# qbI0000115v1_1_1.net
KiCad netlist of a schematic drawn in Altium Designer
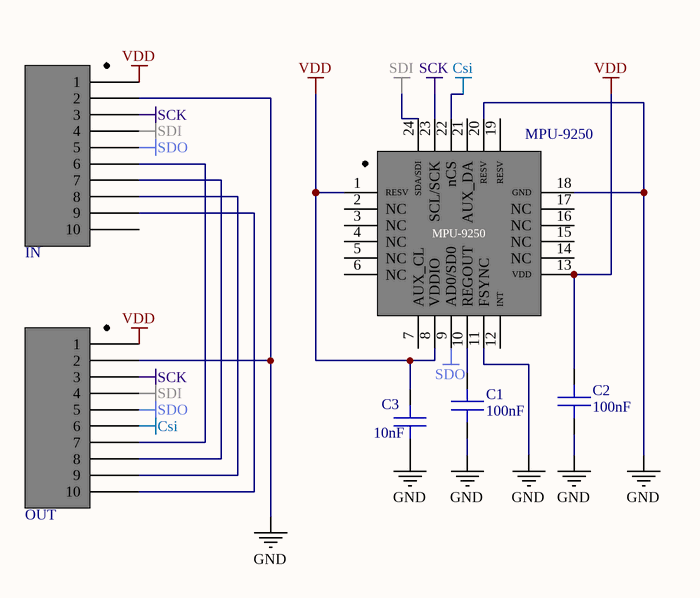
[diagram p0: qbI0000115v1.1.1.SchDoc]

(export (version "E")
  (design (tool "Eeschema 10.0.6"))
  (components
    (comp (ref "C1")
      (value "100nF")
      (footprint "C0603C104K5RACAUTO")
      (description "KEMET 100nF 0603 Cer 50VDC 10% X7R MLCC")
      (libsource (lib "Additional custom library") (part "C0603C104K5RACAUTO"))
    )
    (comp (ref "C2")
      (value "100nF")
      (footprint "C0603C104K5RACAUTO")
      (description "KEMET 100nF 0603 Cer 50VDC 10% X7R MLCC")
      (libsource (lib "Additional custom library") (part "C0603C104K5RACAUTO"))
    )
    (comp (ref "C3")
      (value "10nF")
      (footprint "C0603C103J8RACTU")
      (description "Kemet C 10nF 0603 Cer 10VDC 5% X7R MLCC")
      (fields
        (field (name "MANUFACTURER") "Kemet")
        (field (name "MANUFACTURER PART NUMBER") "C0603C103J8RACTU")
      )
      (libsource (lib "qbCapacitor0603") (part "C0603C103J8RACTU"))
    )
    (comp (ref "IN")
      (value "JST SM10B-XSRS-ETB")
      (footprint "SM10B-XSRS-ETB")
      (description "JST 10WAY angle XSR, SMT, 0.6mm, SM10B-XSRS-ETB")
      (fields (field (name "MANUFACTURER") "JST") (field (name "MANUFACTURER PART NUMBER") "SM10B-XSRS-ETB"))
      (libsource (lib "QB Conn Lib") (part "SM10B-XSRS-ETB"))
    )
    (comp (ref "MPU-9250")
      (value "MPU-9250")
      (footprint "MPU-2950")
      (description "MPU-9250 3X3X1 24QFN")
      (fields (field (name "MANUFACTURER") "InvenSense"))
      (libsource (lib "qbChipset") (part "MPU-9250"))
    )
    (comp (ref "OUT")
      (value "JST SM10B-XSRS-ETB")
      (footprint "SM10B-XSRS-ETB")
      (description "JST 10WAY angle XSR, SMT, 0.6mm, SM10B-XSRS-ETB")
      (fields (field (name "MANUFACTURER") "JST") (field (name "MANUFACTURER PART NUMBER") "SM10B-XSRS-ETB"))
      (libsource (lib "QB Conn Lib") (part "SM10B-XSRS-ETB"))
    )
  )
  (nets
    (net (code "1") (name "Csi") (class "Default")
      (node (ref "MPU-9250") (pin "22") (pinfunction "nCS_22") (pintype "passive"))
      (node (ref "OUT") (pin "6") (pinfunction "6_6") (pintype "passive"))
    )
    (net (code "2") (name "GND") (class "Default")
      (node (ref "C1") (pin "1") (pinfunction "1_1") (pintype "passive"))
      (node (ref "C2") (pin "1") (pinfunction "1_1") (pintype "passive"))
      (node (ref "C3") (pin "1") (pinfunction "1_1") (pintype "passive"))
      (node (ref "IN") (pin "2") (pinfunction "2_2") (pintype "passive"))
      (node (ref "MPU-9250") (pin "11") (pinfunction "FSYNC_11") (pintype "passive"))
      (node (ref "MPU-9250") (pin "18") (pinfunction "GND_18") (pintype "passive"))
      (node (ref "MPU-9250") (pin "20") (pinfunction "RESV_20") (pintype "passive"))
      (node (ref "OUT") (pin "2") (pinfunction "2_2") (pintype "passive"))
    )
    (net (code "3") (name "Net-(IN-Pad6)") (class "Default")
      (node (ref "IN") (pin "6") (pinfunction "6_6") (pintype "passive"))
      (node (ref "OUT") (pin "7") (pinfunction "7_7") (pintype "passive"))
    )
    (net (code "4") (name "Net-(IN-Pad7)") (class "Default")
      (node (ref "IN") (pin "7") (pinfunction "7_7") (pintype "passive"))
      (node (ref "OUT") (pin "8") (pinfunction "8_8") (pintype "passive"))
    )
    (net (code "5") (name "Net-(IN-Pad8)") (class "Default")
      (node (ref "IN") (pin "8") (pinfunction "8_8") (pintype "passive"))
      (node (ref "OUT") (pin "9") (pinfunction "9_9") (pintype "passive"))
    )
    (net (code "6") (name "Net-(IN-Pad9)") (class "Default")
      (node (ref "IN") (pin "9") (pinfunction "9_9") (pintype "passive"))
      (node (ref "OUT") (pin "10") (pinfunction "10_10") (pintype "passive"))
    )
    (net (code "7") (name "Net-(MPU-9250-REGOUT)") (class "Default")
      (node (ref "C1") (pin "2") (pinfunction "2_2") (pintype "passive"))
      (node (ref "MPU-9250") (pin "10") (pinfunction "REGOUT_10") (pintype "passive"))
    )
    (net (code "8") (name "SCK") (class "Default")
      (node (ref "IN") (pin "3") (pinfunction "3_3") (pintype "passive"))
      (node (ref "MPU-9250") (pin "23") (pinfunction "SCL/SCK_23") (pintype "passive"))
      (node (ref "OUT") (pin "3") (pinfunction "3_3") (pintype "passive"))
    )
    (net (code "9") (name "SDI") (class "Default")
      (node (ref "IN") (pin "4") (pinfunction "4_4") (pintype "passive"))
      (node (ref "MPU-9250") (pin "24") (pinfunction "SDA/SDI_24") (pintype "passive"))
      (node (ref "OUT") (pin "4") (pinfunction "4_4") (pintype "passive"))
    )
    (net (code "10") (name "SDO") (class "Default")
      (node (ref "IN") (pin "5") (pinfunction "5_5") (pintype "passive"))
      (node (ref "MPU-9250") (pin "9") (pinfunction "AD0/SD0_9") (pintype "passive"))
      (node (ref "OUT") (pin "5") (pinfunction "5_5") (pintype "passive"))
    )
    (net (code "11") (name "VDD") (class "Default")
      (node (ref "C2") (pin "2") (pinfunction "2_2") (pintype "passive"))
      (node (ref "C3") (pin "2") (pinfunction "2_2") (pintype "passive"))
      (node (ref "IN") (pin "1") (pinfunction "1_1") (pintype "passive"))
      (node (ref "MPU-9250") (pin "1") (pinfunction "RESV_1") (pintype "passive"))
      (node (ref "MPU-9250") (pin "13") (pinfunction "VDD_13") (pintype "passive"))
      (node (ref "MPU-9250") (pin "8") (pinfunction "VDDIO_8") (pintype "passive"))
      (node (ref "OUT") (pin "1") (pinfunction "1_1") (pintype "passive"))
    )
    (net (code "12") (name "unconnected-(IN-Pad10)") (class "Default")
      (node (ref "IN") (pin "10") (pinfunction "10_10") (pintype "passive"))
    )
    (net (code "13") (name "unconnected-(MPU-9250-AUX_CL-Pad7)") (class "Default")
      (node (ref "MPU-9250") (pin "7") (pinfunction "AUX_CL_7") (pintype "passive"))
    )
    (net (code "14") (name "unconnected-(MPU-9250-AUX_DA-Pad21)") (class "Default")
      (node (ref "MPU-9250") (pin "21") (pinfunction "AUX_DA_21") (pintype "passive"))
    )
    (net (code "15") (name "unconnected-(MPU-9250-INT-Pad12)") (class "Default")
      (node (ref "MPU-9250") (pin "12") (pinfunction "INT_12") (pintype "passive"))
    )
    (net (code "16") (name "unconnected-(MPU-9250-NC-Pad2)") (class "Default")
      (node (ref "MPU-9250") (pin "2") (pinfunction "NC_2") (pintype "passive"))
    )
    (net (code "17") (name "unconnected-(MPU-9250-NC-Pad3)") (class "Default")
      (node (ref "MPU-9250") (pin "3") (pinfunction "NC_3") (pintype "passive"))
    )
    (net (code "18") (name "unconnected-(MPU-9250-NC-Pad4)") (class "Default")
      (node (ref "MPU-9250") (pin "4") (pinfunction "NC_4") (pintype "passive"))
    )
    (net (code "19") (name "unconnected-(MPU-9250-NC-Pad5)") (class "Default")
      (node (ref "MPU-9250") (pin "5") (pinfunction "NC_5") (pintype "passive"))
    )
    (net (code "20") (name "unconnected-(MPU-9250-NC-Pad6)") (class "Default")
      (node (ref "MPU-9250") (pin "6") (pinfunction "NC_6") (pintype "passive"))
    )
    (net (code "21") (name "unconnected-(MPU-9250-NC-Pad14)") (class "Default")
      (node (ref "MPU-9250") (pin "14") (pinfunction "NC_14") (pintype "passive"))
    )
    (net (code "22") (name "unconnected-(MPU-9250-NC-Pad15)") (class "Default")
      (node (ref "MPU-9250") (pin "15") (pinfunction "NC_15") (pintype "passive"))
    )
    (net (code "23") (name "unconnected-(MPU-9250-NC-Pad16)") (class "Default")
      (node (ref "MPU-9250") (pin "16") (pinfunction "NC_16") (pintype "passive"))
    )
    (net (code "24") (name "unconnected-(MPU-9250-NC-Pad17)") (class "Default")
      (node (ref "MPU-9250") (pin "17") (pinfunction "NC_17") (pintype "passive"))
    )
    (net (code "25") (name "unconnected-(MPU-9250-RESV-Pad19)") (class "Default")
      (node (ref "MPU-9250") (pin "19") (pinfunction "RESV_19") (pintype "passive"))
    )
  )
)
